# TPS65217DRSLR.net
KiCad netlist of a schematic drawn in Altium Designer
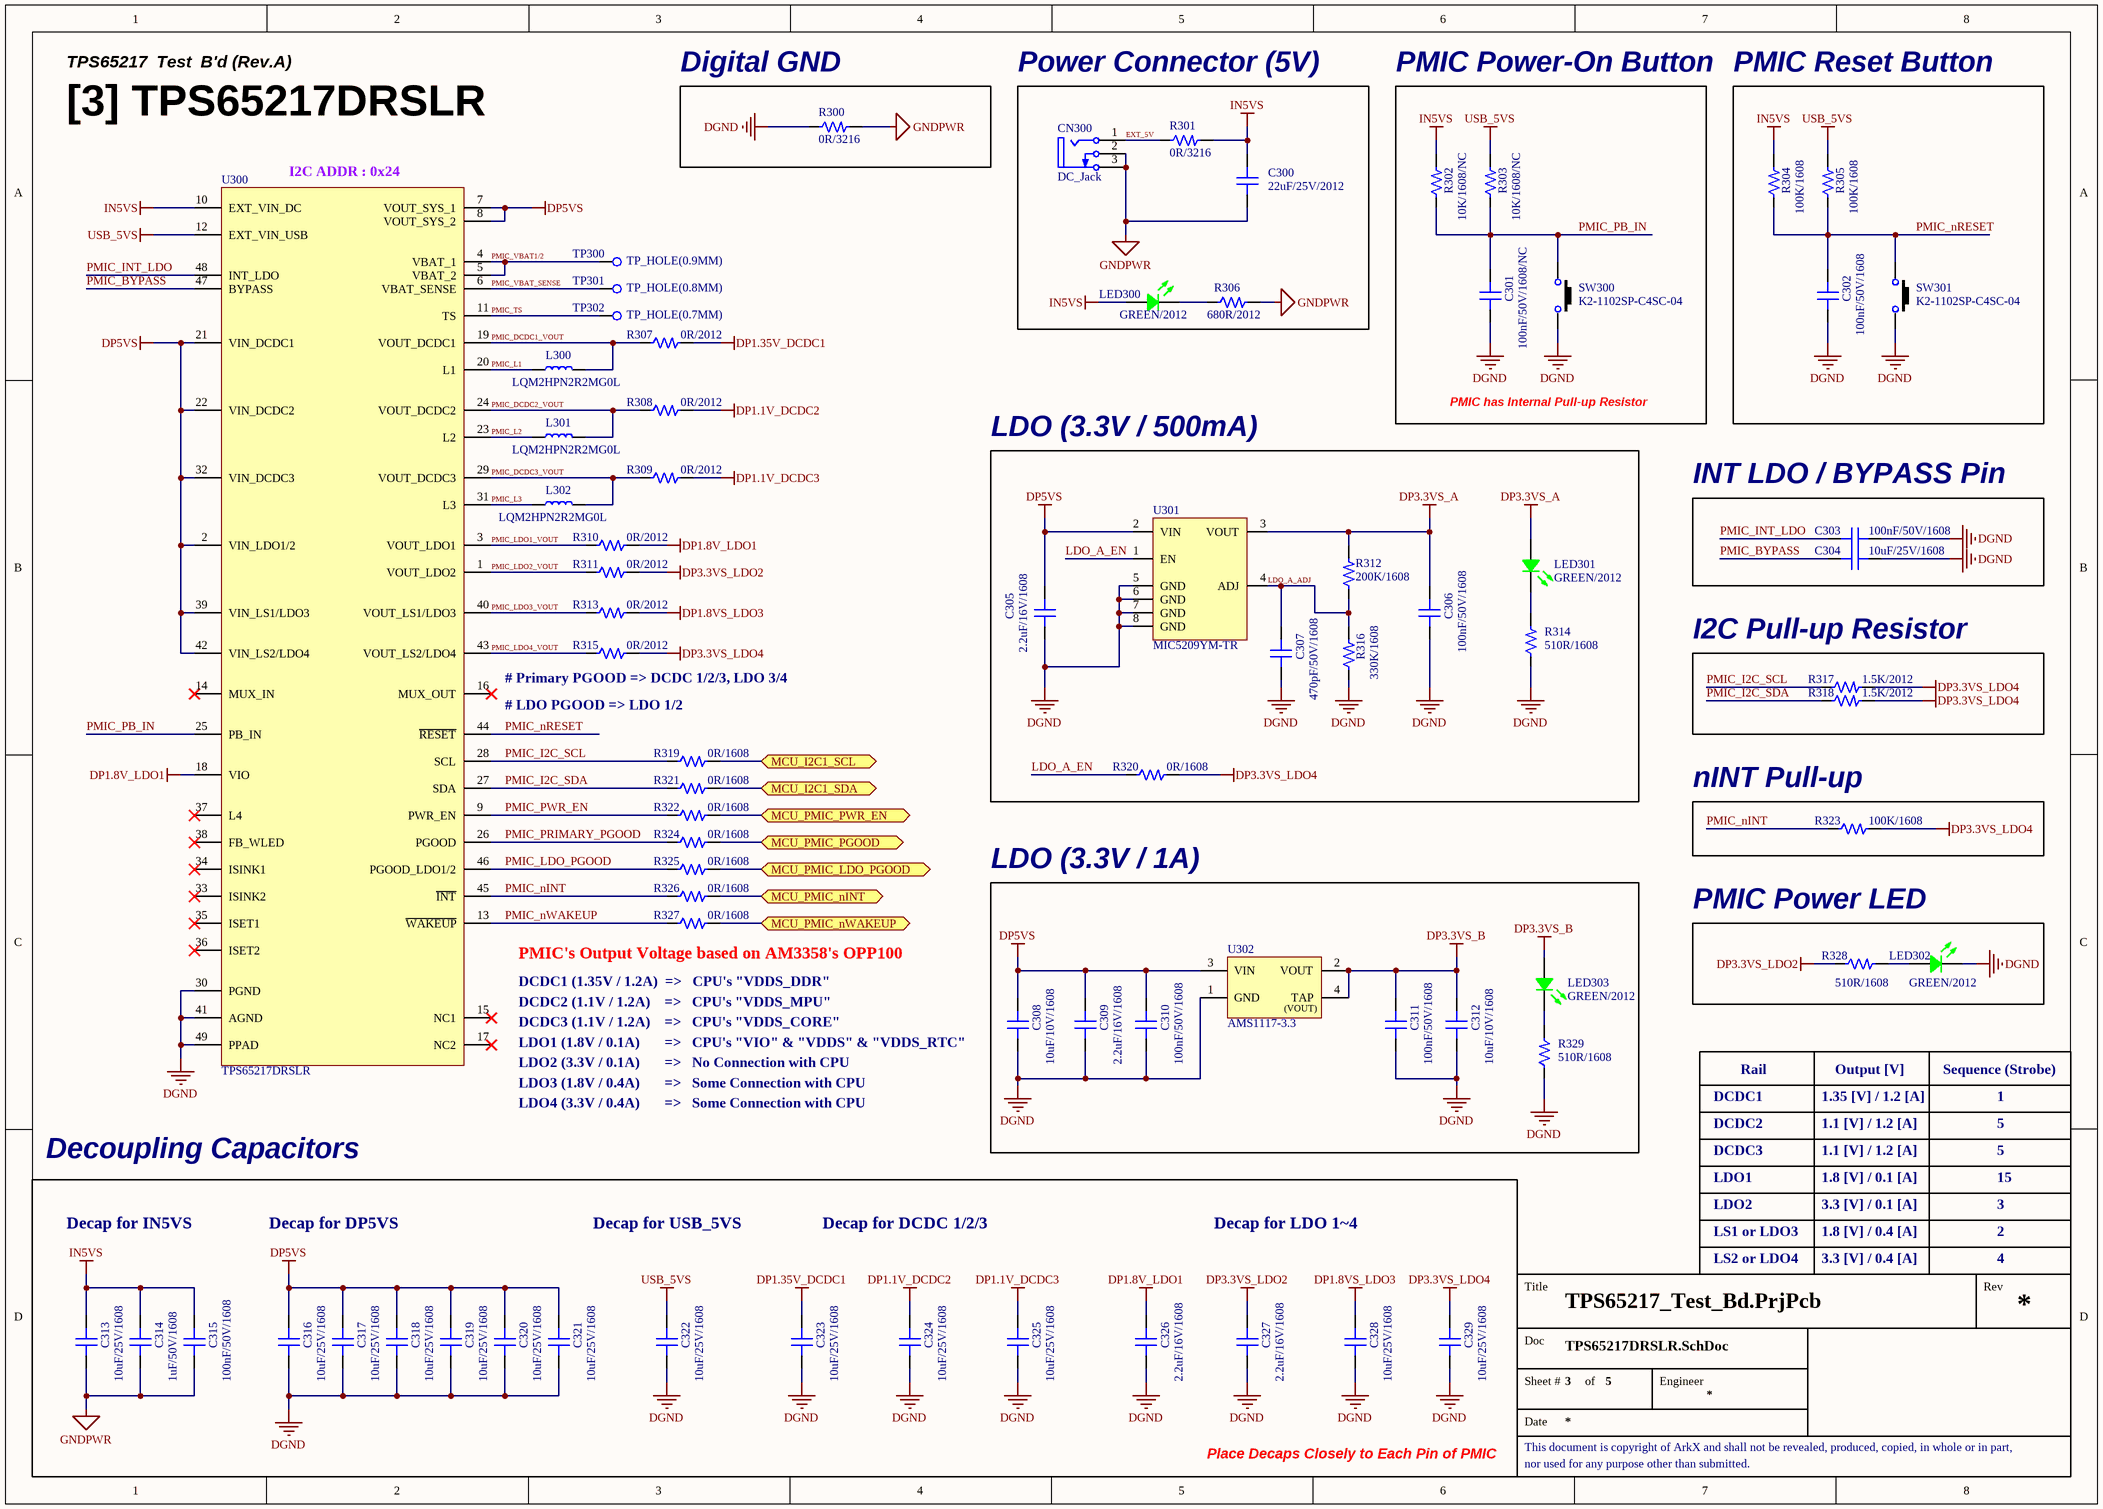
[diagram p0: TPS65217DRSLR.SchDoc]

(export (version "E")
  (design (tool "Eeschema 10.0.6"))
  (components
    (comp (ref "C300")
      (value "22uF/25V/2012")
      (footprint "CAP 2012 (0805_INCH)")
      (description "Ceramic CAP_22uF/25V/2012")
      (fields (field (name "LCSC PART #") "C45783"))
      (libsource (lib "Arkx") (part "CAP_22uF/25V/2012"))
    )
    (comp (ref "C301")
      (value "100nF/50V/1608/NC")
      (footprint "CAP 1608 (0603_INCH)/NC")
      (description "Ceramic CAP_100nF/50V/1608")
      (libsource (lib "Arkx") (part "CAP_NC_100nF/50V/1608"))
    )
    (comp (ref "C302")
      (value "100nF/50V/1608")
      (footprint "CAP 1608 (0603_INCH)")
      (description "Ceramic CAP_100nF/50V/1608")
      (fields (field (name "LCSC PART #") "C14663"))
      (libsource (lib "Arkx") (part "CAP_100nF/50V/1608"))
    )
    (comp (ref "C303")
      (value "100nF/50V/1608")
      (footprint "CAP 1608 (0603_INCH)")
      (description "Ceramic CAP_100nF/50V/1608")
      (fields (field (name "LCSC PART #") "C14663"))
      (libsource (lib "Arkx") (part "CAP_100nF/50V/1608"))
    )
    (comp (ref "C304")
      (value "10uF/25V/1608")
      (footprint "CAP 1608 (0603_INCH)")
      (description "Ceramic CAP_10uF/25V/1608")
      (fields (field (name "LCSC PART #") "C96446"))
      (libsource (lib "Arkx") (part "CAP_10uF/25V/1608"))
    )
    (comp (ref "C305")
      (value "2.2uF/16V/1608")
      (footprint "CAP 1608 (0603_INCH)")
      (description "Ceramic CAP_2.2uF/16V/1608")
      (fields (field (name "LCSC PART #") "C23630"))
      (libsource (lib "Arkx") (part "CAP_2.2uF/16V/1608"))
    )
    (comp (ref "C306")
      (value "100nF/50V/1608")
      (footprint "CAP 1608 (0603_INCH)")
      (description "Ceramic CAP_100nF/50V/1608")
      (fields (field (name "LCSC PART #") "C14663"))
      (libsource (lib "Arkx") (part "CAP_100nF/50V/1608"))
    )
    (comp (ref "C307")
      (value "470pF/50V/1608")
      (footprint "CAP 1608 (0603_INCH)")
      (description "Ceramic CAP_470pF/50V/1608")
      (fields (field (name "LCSC PART #") "C1620"))
      (libsource (lib "Arkx") (part "CAP_470pF/50V/1608"))
    )
    (comp (ref "C308")
      (value "10uF/10V/1608")
      (footprint "CAP 1608 (0603_INCH)")
      (description "Ceramic CAP_10uF/10V/1608")
      (fields (field (name "LCSC PART #") "C19702"))
      (libsource (lib "Arkx") (part "CAP_10uF/10V/1608"))
    )
    (comp (ref "C309")
      (value "2.2uF/16V/1608")
      (footprint "CAP 1608 (0603_INCH)")
      (description "Ceramic CAP_2.2uF/16V/1608")
      (fields (field (name "LCSC PART #") "C23630"))
      (libsource (lib "Arkx") (part "CAP_2.2uF/16V/1608"))
    )
    (comp (ref "C310")
      (value "100nF/50V/1608")
      (footprint "CAP 1608 (0603_INCH)")
      (description "Ceramic CAP_100nF/50V/1608")
      (fields (field (name "LCSC PART #") "C14663"))
      (libsource (lib "Arkx") (part "CAP_100nF/50V/1608"))
    )
    (comp (ref "C311")
      (value "100nF/50V/1608")
      (footprint "CAP 1608 (0603_INCH)")
      (description "Ceramic CAP_100nF/50V/1608")
      (fields (field (name "LCSC PART #") "C14663"))
      (libsource (lib "Arkx") (part "CAP_100nF/50V/1608"))
    )
    (comp (ref "C312")
      (value "10uF/10V/1608")
      (footprint "CAP 1608 (0603_INCH)")
      (description "Ceramic CAP_10uF/10V/1608")
      (fields (field (name "LCSC PART #") "C19702"))
      (libsource (lib "Arkx") (part "CAP_10uF/10V/1608"))
    )
    (comp (ref "C313")
      (value "10uF/25V/1608")
      (footprint "CAP 1608 (0603_INCH)")
      (description "Ceramic CAP_10uF/25V/1608")
      (fields (field (name "LCSC PART #") "C96446"))
      (libsource (lib "Arkx") (part "CAP_10uF/25V/1608"))
    )
    (comp (ref "C314")
      (value "1uF/50V/1608")
      (footprint "CAP 1608 (0603_INCH)")
      (description "Ceramic CAP_1uF/50V/1608")
      (fields (field (name "LCSC PART #") "C15849"))
      (libsource (lib "Arkx") (part "CAP_1uF/50V/1608"))
    )
    (comp (ref "C315")
      (value "100nF/50V/1608")
      (footprint "CAP 1608 (0603_INCH)")
      (description "Ceramic CAP_100nF/50V/1608")
      (fields (field (name "LCSC PART #") "C14663"))
      (libsource (lib "Arkx") (part "CAP_100nF/50V/1608"))
    )
    (comp (ref "C316")
      (value "10uF/25V/1608")
      (footprint "CAP 1608 (0603_INCH)")
      (description "Ceramic CAP_10uF/25V/1608")
      (fields (field (name "LCSC PART #") "C96446"))
      (libsource (lib "Arkx") (part "CAP_10uF/25V/1608"))
    )
    (comp (ref "C317")
      (value "10uF/25V/1608")
      (footprint "CAP 1608 (0603_INCH)")
      (description "Ceramic CAP_10uF/25V/1608")
      (fields (field (name "LCSC PART #") "C96446"))
      (libsource (lib "Arkx") (part "CAP_10uF/25V/1608"))
    )
    (comp (ref "C318")
      (value "10uF/25V/1608")
      (footprint "CAP 1608 (0603_INCH)")
      (description "Ceramic CAP_10uF/25V/1608")
      (fields (field (name "LCSC PART #") "C96446"))
      (libsource (lib "Arkx") (part "CAP_10uF/25V/1608"))
    )
    (comp (ref "C319")
      (value "10uF/25V/1608")
      (footprint "CAP 1608 (0603_INCH)")
      (description "Ceramic CAP_10uF/25V/1608")
      (fields (field (name "LCSC PART #") "C96446"))
      (libsource (lib "Arkx") (part "CAP_10uF/25V/1608"))
    )
    (comp (ref "C320")
      (value "10uF/25V/1608")
      (footprint "CAP 1608 (0603_INCH)")
      (description "Ceramic CAP_10uF/25V/1608")
      (fields (field (name "LCSC PART #") "C96446"))
      (libsource (lib "Arkx") (part "CAP_10uF/25V/1608"))
    )
    (comp (ref "C321")
      (value "10uF/25V/1608")
      (footprint "CAP 1608 (0603_INCH)")
      (description "Ceramic CAP_10uF/25V/1608")
      (fields (field (name "LCSC PART #") "C96446"))
      (libsource (lib "Arkx") (part "CAP_10uF/25V/1608"))
    )
    (comp (ref "C322")
      (value "10uF/25V/1608")
      (footprint "CAP 1608 (0603_INCH)")
      (description "Ceramic CAP_10uF/25V/1608")
      (fields (field (name "LCSC PART #") "C96446"))
      (libsource (lib "Arkx") (part "CAP_10uF/25V/1608"))
    )
    (comp (ref "C323")
      (value "10uF/25V/1608")
      (footprint "CAP 1608 (0603_INCH)")
      (description "Ceramic CAP_10uF/25V/1608")
      (fields (field (name "LCSC PART #") "C96446"))
      (libsource (lib "Arkx") (part "CAP_10uF/25V/1608"))
    )
    (comp (ref "C324")
      (value "10uF/25V/1608")
      (footprint "CAP 1608 (0603_INCH)")
      (description "Ceramic CAP_10uF/25V/1608")
      (fields (field (name "LCSC PART #") "C96446"))
      (libsource (lib "Arkx") (part "CAP_10uF/25V/1608"))
    )
    (comp (ref "C325")
      (value "10uF/25V/1608")
      (footprint "CAP 1608 (0603_INCH)")
      (description "Ceramic CAP_10uF/25V/1608")
      (fields (field (name "LCSC PART #") "C96446"))
      (libsource (lib "Arkx") (part "CAP_10uF/25V/1608"))
    )
    (comp (ref "C326")
      (value "2.2uF/16V/1608")
      (footprint "CAP 1608 (0603_INCH)")
      (description "Ceramic CAP_2.2uF/16V/1608")
      (fields (field (name "LCSC PART #") "C23630"))
      (libsource (lib "Arkx") (part "CAP_2.2uF/16V/1608"))
    )
    (comp (ref "C327")
      (value "2.2uF/16V/1608")
      (footprint "CAP 1608 (0603_INCH)")
      (description "Ceramic CAP_2.2uF/16V/1608")
      (fields (field (name "LCSC PART #") "C23630"))
      (libsource (lib "Arkx") (part "CAP_2.2uF/16V/1608"))
    )
    (comp (ref "C328")
      (value "10uF/25V/1608")
      (footprint "CAP 1608 (0603_INCH)")
      (description "Ceramic CAP_10uF/25V/1608")
      (fields (field (name "LCSC PART #") "C96446"))
      (libsource (lib "Arkx") (part "CAP_10uF/25V/1608"))
    )
    (comp (ref "C329")
      (value "10uF/25V/1608")
      (footprint "CAP 1608 (0603_INCH)")
      (description "Ceramic CAP_10uF/25V/1608")
      (fields (field (name "LCSC PART #") "C96446"))
      (libsource (lib "Arkx") (part "CAP_10uF/25V/1608"))
    )
    (comp (ref "CN300")
      (value "DC_Jack")
      (footprint "CON_DC-JACK")
      (libsource (lib "Arkx") (part "CON_DC-Jack"))
    )
    (comp (ref "L300")
      (value "LQM2HPN2R2MG0L")
      (footprint "IND_LQM2HPN2R2MG0L")
      (description "2.2 µH Shielded Multilayer Inductor 1.3 A 100mOhm Max 1008 (2520 Metric)")
      (fields (field (name "LCSC PART #") "C86092"))
      (libsource (lib "Arkx") (part "IND_LQM2HPN2R2MG0L"))
    )
    (comp (ref "L301")
      (value "LQM2HPN2R2MG0L")
      (footprint "IND_LQM2HPN2R2MG0L")
      (description "2.2 µH Shielded Multilayer Inductor 1.3 A 100mOhm Max 1008 (2520 Metric)")
      (fields (field (name "LCSC PART #") "C86092"))
      (libsource (lib "Arkx") (part "IND_LQM2HPN2R2MG0L"))
    )
    (comp (ref "L302")
      (value "LQM2HPN2R2MG0L")
      (footprint "IND_LQM2HPN2R2MG0L")
      (description "2.2 µH Shielded Multilayer Inductor 1.3 A 100mOhm Max 1008 (2520 Metric)")
      (fields (field (name "LCSC PART #") "C86092"))
      (libsource (lib "Arkx") (part "IND_LQM2HPN2R2MG0L"))
    )
    (comp (ref "LED300")
      (value "GREEN/2012")
      (footprint "LED MHT170RGBCT (GREEN)")
      (fields (field (name "LCSC PART #") "C2962094"))
      (libsource (lib "Arkx") (part "LED_MHT170RGBCT(GREEN)"))
    )
    (comp (ref "LED301")
      (value "GREEN/2012")
      (footprint "LED MHT170RGBCT (GREEN)")
      (fields (field (name "LCSC PART #") "C2962094"))
      (libsource (lib "Arkx") (part "LED_MHT170RGBCT(GREEN)"))
    )
    (comp (ref "LED302")
      (value "GREEN/2012")
      (footprint "LED MHT170RGBCT (GREEN)")
      (fields (field (name "LCSC PART #") "C2962094"))
      (libsource (lib "Arkx") (part "LED_MHT170RGBCT(GREEN)"))
    )
    (comp (ref "LED303")
      (value "GREEN/2012")
      (footprint "LED MHT170RGBCT (GREEN)")
      (fields (field (name "LCSC PART #") "C2962094"))
      (libsource (lib "Arkx") (part "LED_MHT170RGBCT(GREEN)"))
    )
    (comp (ref "R300")
      (value "0R/3216")
      (footprint "RES 3216 (1206_inch)")
      (description "RES_0R/3216/0.25W")
      (fields (field (name "LCSC PART #") "C17888"))
      (libsource (lib "Arkx") (part "RES_0R/3216/0.25W"))
    )
    (comp (ref "R301")
      (value "0R/3216")
      (footprint "RES 3216 (1206_inch)")
      (description "RES_0R/3216/0.25W")
      (fields (field (name "LCSC PART #") "C17888"))
      (libsource (lib "Arkx") (part "RES_0R/3216/0.25W"))
    )
    (comp (ref "R302")
      (value "10K/1608/NC")
      (footprint "RES 1608 (0603_inch)/NC")
      (description "RES_10K/1608/0.1W")
      (libsource (lib "Arkx") (part "RES_NC_10K/1608/0.1W"))
    )
    (comp (ref "R303")
      (value "10K/1608/NC")
      (footprint "RES 1608 (0603_inch)/NC")
      (description "RES_10K/1608/0.1W")
      (libsource (lib "Arkx") (part "RES_NC_10K/1608/0.1W"))
    )
    (comp (ref "R304")
      (value "100K/1608")
      (footprint "RES 1608 (0603_inch)")
      (description "RES_100K/1608/0.1W")
      (fields (field (name "LCSC PART #") "C25803"))
      (libsource (lib "Arkx") (part "RES_100K/1608/0.1W"))
    )
    (comp (ref "R305")
      (value "100K/1608")
      (footprint "RES 1608 (0603_inch)")
      (description "RES_100K/1608/0.1W")
      (fields (field (name "LCSC PART #") "C25803"))
      (libsource (lib "Arkx") (part "RES_100K/1608/0.1W"))
    )
    (comp (ref "R306")
      (value "680R/2012")
      (footprint "RES 2012 (0805_inch)")
      (description "RES_680R/2012/0.125W")
      (fields (field (name "LCSC PART #") "C17798"))
      (libsource (lib "Arkx") (part "RES_680R/2012/0.125W"))
    )
    (comp (ref "R307")
      (value "0R/2012")
      (footprint "RES 2012 (0805_inch)")
      (description "RES_0R/2012/0.125W")
      (fields (field (name "LCSC PART #") "C17477"))
      (libsource (lib "Arkx") (part "RES_0R/2012/0.125W"))
    )
    (comp (ref "R308")
      (value "0R/2012")
      (footprint "RES 2012 (0805_inch)")
      (description "RES_0R/2012/0.125W")
      (fields (field (name "LCSC PART #") "C17477"))
      (libsource (lib "Arkx") (part "RES_0R/2012/0.125W"))
    )
    (comp (ref "R309")
      (value "0R/2012")
      (footprint "RES 2012 (0805_inch)")
      (description "RES_0R/2012/0.125W")
      (fields (field (name "LCSC PART #") "C17477"))
      (libsource (lib "Arkx") (part "RES_0R/2012/0.125W"))
    )
    (comp (ref "R310")
      (value "0R/2012")
      (footprint "RES 2012 (0805_inch)")
      (description "RES_0R/2012/0.125W")
      (fields (field (name "LCSC PART #") "C17477"))
      (libsource (lib "Arkx") (part "RES_0R/2012/0.125W"))
    )
    (comp (ref "R311")
      (value "0R/2012")
      (footprint "RES 2012 (0805_inch)")
      (description "RES_0R/2012/0.125W")
      (fields (field (name "LCSC PART #") "C17477"))
      (libsource (lib "Arkx") (part "RES_0R/2012/0.125W"))
    )
    (comp (ref "R312")
      (value "200K/1608")
      (footprint "RES 1608 (0603_inch)")
      (description "RES_200K/1608/0.1W")
      (fields (field (name "LCSC PART #") "C25811"))
      (libsource (lib "Arkx") (part "RES_200K/1608/0.1W"))
    )
    (comp (ref "R313")
      (value "0R/2012")
      (footprint "RES 2012 (0805_inch)")
      (description "RES_0R/2012/0.125W")
      (fields (field (name "LCSC PART #") "C17477"))
      (libsource (lib "Arkx") (part "RES_0R/2012/0.125W"))
    )
    (comp (ref "R314")
      (value "510R/1608")
      (footprint "RES 1608 (0603_inch)")
      (description "RES_510R/1608/0.1W")
      (fields (field (name "LCSC PART #") "C23193"))
      (libsource (lib "Arkx") (part "RES_510R/1608/0.1W"))
    )
    (comp (ref "R315")
      (value "0R/2012")
      (footprint "RES 2012 (0805_inch)")
      (description "RES_0R/2012/0.125W")
      (fields (field (name "LCSC PART #") "C17477"))
      (libsource (lib "Arkx") (part "RES_0R/2012/0.125W"))
    )
    (comp (ref "R316")
      (value "330K/1608")
      (footprint "RES 1608 (0603_inch)")
      (description "RES_330K/1608/0.1W")
      (fields (field (name "LCSC PART #") "C23137"))
      (libsource (lib "Arkx") (part "RES_330K/1608/0.1W"))
    )
    (comp (ref "R317")
      (value "1.5K/2012")
      (footprint "RES 2012 (0805_inch)")
      (description "RES_1.5K/2012/0.125W")
      (fields (field (name "LCSC PART #") "C4310"))
      (libsource (lib "Arkx") (part "RES_1.5K/2012/0.125W"))
    )
    (comp (ref "R318")
      (value "1.5K/2012")
      (footprint "RES 2012 (0805_inch)")
      (description "RES_1.5K/2012/0.125W")
      (fields (field (name "LCSC PART #") "C4310"))
      (libsource (lib "Arkx") (part "RES_1.5K/2012/0.125W"))
    )
    (comp (ref "R319")
      (value "0R/1608")
      (footprint "RES 1608 (0603_inch)")
      (description "RES_0R/1608/0.1W")
      (fields (field (name "LCSC PART #") "C21189"))
      (libsource (lib "Arkx") (part "RES_0R/1608/0.1W"))
    )
    (comp (ref "R320")
      (value "0R/1608")
      (footprint "RES 1608 (0603_inch)")
      (description "RES_0R/1608/0.1W")
      (fields (field (name "LCSC PART #") "C21189"))
      (libsource (lib "Arkx") (part "RES_0R/1608/0.1W"))
    )
    (comp (ref "R321")
      (value "0R/1608")
      (footprint "RES 1608 (0603_inch)")
      (description "RES_0R/1608/0.1W")
      (fields (field (name "LCSC PART #") "C21189"))
      (libsource (lib "Arkx") (part "RES_0R/1608/0.1W"))
    )
    (comp (ref "R322")
      (value "0R/1608")
      (footprint "RES 1608 (0603_inch)")
      (description "RES_0R/1608/0.1W")
      (fields (field (name "LCSC PART #") "C21189"))
      (libsource (lib "Arkx") (part "RES_0R/1608/0.1W"))
    )
    (comp (ref "R323")
      (value "100K/1608")
      (footprint "RES 1608 (0603_inch)")
      (description "RES_100K/1608/0.1W")
      (fields (field (name "LCSC PART #") "C25803"))
      (libsource (lib "Arkx") (part "RES_100K/1608/0.1W"))
    )
    (comp (ref "R324")
      (value "0R/1608")
      (footprint "RES 1608 (0603_inch)")
      (description "RES_0R/1608/0.1W")
      (fields (field (name "LCSC PART #") "C21189"))
      (libsource (lib "Arkx") (part "RES_0R/1608/0.1W"))
    )
    (comp (ref "R325")
      (value "0R/1608")
      (footprint "RES 1608 (0603_inch)")
      (description "RES_0R/1608/0.1W")
      (fields (field (name "LCSC PART #") "C21189"))
      (libsource (lib "Arkx") (part "RES_0R/1608/0.1W"))
    )
    (comp (ref "R326")
      (value "0R/1608")
      (footprint "RES 1608 (0603_inch)")
      (description "RES_0R/1608/0.1W")
      (fields (field (name "LCSC PART #") "C21189"))
      (libsource (lib "Arkx") (part "RES_0R/1608/0.1W"))
    )
    (comp (ref "R327")
      (value "0R/1608")
      (footprint "RES 1608 (0603_inch)")
      (description "RES_0R/1608/0.1W")
      (fields (field (name "LCSC PART #") "C21189"))
      (libsource (lib "Arkx") (part "RES_0R/1608/0.1W"))
    )
    (comp (ref "R328")
      (value "510R/1608")
      (footprint "RES 1608 (0603_inch)")
      (description "RES_510R/1608/0.1W")
      (fields (field (name "LCSC PART #") "C23193"))
      (libsource (lib "Arkx") (part "RES_510R/1608/0.1W"))
    )
    (comp (ref "R329")
      (value "510R/1608")
      (footprint "RES 1608 (0603_inch)")
      (description "RES_510R/1608/0.1W")
      (fields (field (name "LCSC PART #") "C23193"))
      (libsource (lib "Arkx") (part "RES_510R/1608/0.1W"))
    )
    (comp (ref "SW300")
      (value "K2-1102SP-C4SC-04")
      (footprint "SW K2-1102SP-C4SC-04")
      (fields (field (name "LCSC PART #") "C127509"))
      (libsource (lib "Arkx") (part "SW_K2-1102SP-C4SC-04(2P)"))
    )
    (comp (ref "SW301")
      (value "K2-1102SP-C4SC-04")
      (footprint "SW K2-1102SP-C4SC-04")
      (fields (field (name "LCSC PART #") "C127509"))
      (libsource (lib "Arkx") (part "SW_K2-1102SP-C4SC-04(2P)"))
    )
    (comp (ref "TP300")
      (value "TP_HOLE(0.9MM)")
      (footprint "TP_HOLE(0.9MM)")
      (libsource (lib "Arkx") (part "TP_HOLE(0.9MM)"))
    )
    (comp (ref "TP301")
      (value "TP_HOLE(0.8MM)")
      (footprint "TP_HOLE(0.8MM)")
      (libsource (lib "Arkx") (part "TP_HOLE(0.8MM)"))
    )
    (comp (ref "TP302")
      (value "TP_HOLE(0.7MM)")
      (footprint "TP_HOLE(0.7MM)")
      (libsource (lib "Arkx") (part "TP_HOLE(0.7MM)"))
    )
    (comp (ref "U300")
      (value "TPS65217DRSLR")
      (footprint "IC_VQFN-48(6x6)")
      (fields (field (name "LCSC PART #") "C702315"))
      (libsource (lib "Arkx") (part "IC_PMIC_TPS65217DRSLR"))
    )
    (comp (ref "U301")
      (value "MIC5209YM-TR")
      (footprint "IC_SOIC-8 (4.90x3.90mm)")
      (description "Linear Voltage Regulator IC Positive Adjustable 1 Output 500mA 8-SOIC")
      (fields (field (name "LCSC PART #") "C461593"))
      (libsource (lib "Arkx") (part "IC_REG_MIC5209YM-TR"))
    )
    (comp (ref "U302")
      (value "AMS1117-3.3")
      (footprint "SOT 223-3 (DIODES INCORPORATED)")
      (fields (field (name "LCSC PART #") "C6186"))
      (libsource (lib "Arkx") (part "IC_REG_AMS1117-3.3"))
    )
  )
  (nets
    (net (code "1") (name "/EXT_5V") (class "Default")
      (node (ref "CN300") (pin "1") (pinfunction "VCC_1") (pintype "power_in"))
      (node (ref "R301") (pin "1") (pinfunction "1_1") (pintype "passive"))
    )
    (net (code "2") (name "/LDO_A_ADJ") (class "Default")
      (node (ref "C307") (pin "2") (pinfunction "2_2") (pintype "passive"))
      (node (ref "R312") (pin "1") (pinfunction "1_1") (pintype "passive"))
      (node (ref "R316") (pin "2") (pinfunction "2_2") (pintype "passive"))
      (node (ref "U301") (pin "4") (pinfunction "ADJ_4") (pintype "passive"))
    )
    (net (code "3") (name "/LDO_A_EN") (class "Default")
      (node (ref "R320") (pin "1") (pinfunction "1_1") (pintype "passive"))
      (node (ref "U301") (pin "1") (pinfunction "EN_1") (pintype "passive"))
    )
    (net (code "4") (name "/MCU_I2C1_SCL") (class "Default")
      (node (ref "R319") (pin "2") (pinfunction "2_2") (pintype "passive"))
    )
    (net (code "5") (name "/MCU_I2C1_SDA") (class "Default")
      (node (ref "R321") (pin "2") (pinfunction "2_2") (pintype "passive"))
    )
    (net (code "6") (name "/MCU_PMIC_LDO_PGOOD") (class "Default")
      (node (ref "R325") (pin "2") (pinfunction "2_2") (pintype "passive"))
    )
    (net (code "7") (name "/MCU_PMIC_PGOOD") (class "Default")
      (node (ref "R324") (pin "2") (pinfunction "2_2") (pintype "passive"))
    )
    (net (code "8") (name "/MCU_PMIC_PWR_EN") (class "Default")
      (node (ref "R322") (pin "2") (pinfunction "2_2") (pintype "passive"))
    )
    (net (code "9") (name "/MCU_PMIC_nINT") (class "Default")
      (node (ref "R326") (pin "2") (pinfunction "2_2") (pintype "passive"))
    )
    (net (code "10") (name "/MCU_PMIC_nWAKEUP") (class "Default")
      (node (ref "R327") (pin "2") (pinfunction "2_2") (pintype "passive"))
    )
    (net (code "11") (name "/PMIC_BYPASS") (class "Default")
      (node (ref "C304") (pin "2") (pinfunction "2_2") (pintype "passive"))
      (node (ref "U300") (pin "47") (pinfunction "BYPASS_47") (pintype "passive"))
    )
    (net (code "12") (name "/PMIC_DCDC1_VOUT") (class "Default")
      (node (ref "L300") (pin "2") (pinfunction "2_2") (pintype "passive"))
      (node (ref "R307") (pin "1") (pinfunction "1_1") (pintype "passive"))
      (node (ref "U300") (pin "19") (pinfunction "VOUT_DCDC1_19") (pintype "passive"))
    )
    (net (code "13") (name "/PMIC_DCDC2_VOUT") (class "Default")
      (node (ref "L301") (pin "2") (pinfunction "2_2") (pintype "passive"))
      (node (ref "R308") (pin "1") (pinfunction "1_1") (pintype "passive"))
      (node (ref "U300") (pin "24") (pinfunction "VOUT_DCDC2_24") (pintype "passive"))
    )
    (net (code "14") (name "/PMIC_DCDC3_VOUT") (class "Default")
      (node (ref "L302") (pin "2") (pinfunction "2_2") (pintype "passive"))
      (node (ref "R309") (pin "1") (pinfunction "1_1") (pintype "passive"))
      (node (ref "U300") (pin "29") (pinfunction "VOUT_DCDC3_29") (pintype "passive"))
    )
    (net (code "15") (name "/PMIC_I2C_SCL") (class "Default")
      (node (ref "R317") (pin "1") (pinfunction "1_1") (pintype "passive"))
      (node (ref "R319") (pin "1") (pinfunction "1_1") (pintype "passive"))
      (node (ref "U300") (pin "28") (pinfunction "SCL_28") (pintype "passive"))
    )
    (net (code "16") (name "/PMIC_I2C_SDA") (class "Default")
      (node (ref "R318") (pin "1") (pinfunction "1_1") (pintype "passive"))
      (node (ref "R321") (pin "1") (pinfunction "1_1") (pintype "passive"))
      (node (ref "U300") (pin "27") (pinfunction "SDA_27") (pintype "passive"))
    )
    (net (code "17") (name "/PMIC_INT_LDO") (class "Default")
      (node (ref "C303") (pin "2") (pinfunction "2_2") (pintype "passive"))
      (node (ref "U300") (pin "48") (pinfunction "INT_LDO_48") (pintype "passive"))
    )
    (net (code "18") (name "/PMIC_L1") (class "Default")
      (node (ref "L300") (pin "1") (pinfunction "1_1") (pintype "passive"))
      (node (ref "U300") (pin "20") (pinfunction "L1_20") (pintype "passive"))
    )
    (net (code "19") (name "/PMIC_L2") (class "Default")
      (node (ref "L301") (pin "1") (pinfunction "1_1") (pintype "passive"))
      (node (ref "U300") (pin "23") (pinfunction "L2_23") (pintype "passive"))
    )
    (net (code "20") (name "/PMIC_L3") (class "Default")
      (node (ref "L302") (pin "1") (pinfunction "1_1") (pintype "passive"))
      (node (ref "U300") (pin "31") (pinfunction "L3_31") (pintype "passive"))
    )
    (net (code "21") (name "/PMIC_LDO1_VOUT") (class "Default")
      (node (ref "R310") (pin "1") (pinfunction "1_1") (pintype "passive"))
      (node (ref "U300") (pin "3") (pinfunction "VOUT_LDO1_3") (pintype "passive"))
    )
    (net (code "22") (name "/PMIC_LDO2_VOUT") (class "Default")
      (node (ref "R311") (pin "1") (pinfunction "1_1") (pintype "passive"))
      (node (ref "U300") (pin "1") (pinfunction "VOUT_LDO2_1") (pintype "passive"))
    )
    (net (code "23") (name "/PMIC_LDO3_VOUT") (class "Default")
      (node (ref "R313") (pin "1") (pinfunction "1_1") (pintype "passive"))
      (node (ref "U300") (pin "40") (pinfunction "VOUT_LS1/LDO3_40") (pintype "passive"))
    )
    (net (code "24") (name "/PMIC_LDO4_VOUT") (class "Default")
      (node (ref "R315") (pin "1") (pinfunction "1_1") (pintype "passive"))
      (node (ref "U300") (pin "43") (pinfunction "VOUT_LS2/LDO4_43") (pintype "passive"))
    )
    (net (code "25") (name "/PMIC_LDO_PGOOD") (class "Default")
      (node (ref "R325") (pin "1") (pinfunction "1_1") (pintype "passive"))
      (node (ref "U300") (pin "46") (pinfunction "PGOOD_LDO1/2_46") (pintype "passive"))
    )
    (net (code "26") (name "/PMIC_PB_IN") (class "Default")
      (node (ref "C301") (pin "2") (pinfunction "2_2") (pintype "passive"))
      (node (ref "R302") (pin "1") (pinfunction "1_1") (pintype "passive"))
      (node (ref "R303") (pin "1") (pinfunction "1_1") (pintype "passive"))
      (node (ref "SW300") (pin "1") (pinfunction "1_1") (pintype "passive"))
      (node (ref "U300") (pin "25") (pinfunction "PB_IN_25") (pintype "passive"))
    )
    (net (code "27") (name "/PMIC_PRIMARY_PGOOD") (class "Default")
      (node (ref "R324") (pin "1") (pinfunction "1_1") (pintype "passive"))
      (node (ref "U300") (pin "26") (pinfunction "PGOOD_26") (pintype "passive"))
    )
    (net (code "28") (name "/PMIC_PWR_EN") (class "Default")
      (node (ref "R322") (pin "1") (pinfunction "1_1") (pintype "passive"))
      (node (ref "U300") (pin "9") (pinfunction "PWR_EN_9") (pintype "passive"))
    )
    (net (code "29") (name "/PMIC_TS") (class "Default")
      (node (ref "TP302") (pin "1") (pinfunction "TP_1") (pintype "passive"))
      (node (ref "U300") (pin "11") (pinfunction "TS_11") (pintype "passive"))
    )
    (net (code "30") (name "/PMIC_VBAT1{slash}2") (class "Default")
      (node (ref "TP300") (pin "1") (pinfunction "TP_1") (pintype "passive"))
      (node (ref "U300") (pin "4") (pinfunction "VBAT_1_4") (pintype "passive"))
      (node (ref "U300") (pin "5") (pinfunction "VBAT_2_5") (pintype "passive"))
    )
    (net (code "31") (name "/PMIC_VBAT_SENSE") (class "Default")
      (node (ref "TP301") (pin "1") (pinfunction "TP_1") (pintype "passive"))
      (node (ref "U300") (pin "6") (pinfunction "VBAT_SENSE_6") (pintype "passive"))
    )
    (net (code "32") (name "/PMIC_nINT") (class "Default")
      (node (ref "R323") (pin "1") (pinfunction "1_1") (pintype "passive"))
      (node (ref "R326") (pin "1") (pinfunction "1_1") (pintype "passive"))
      (node (ref "U300") (pin "45") (pinfunction "~{INT}_45") (pintype "passive"))
    )
    (net (code "33") (name "/PMIC_nRESET") (class "Default")
      (node (ref "C302") (pin "2") (pinfunction "2_2") (pintype "passive"))
      (node (ref "R304") (pin "1") (pinfunction "1_1") (pintype "passive"))
      (node (ref "R305") (pin "1") (pinfunction "1_1") (pintype "passive"))
      (node (ref "SW301") (pin "1") (pinfunction "1_1") (pintype "passive"))
      (node (ref "U300") (pin "44") (pinfunction "~{RESET}_44") (pintype "passive"))
    )
    (net (code "34") (name "/PMIC_nWAKEUP") (class "Default")
      (node (ref "R327") (pin "1") (pinfunction "1_1") (pintype "passive"))
      (node (ref "U300") (pin "13") (pinfunction "~{WAKEUP}_13") (pintype "passive"))
    )
    (net (code "35") (name "DGND") (class "Default")
      (node (ref "C301") (pin "1") (pinfunction "1_1") (pintype "passive"))
      (node (ref "C302") (pin "1") (pinfunction "1_1") (pintype "passive"))
      (node (ref "C303") (pin "1") (pinfunction "1_1") (pintype "passive"))
      (node (ref "C304") (pin "1") (pinfunction "1_1") (pintype "passive"))
      (node (ref "C305") (pin "1") (pinfunction "1_1") (pintype "passive"))
      (node (ref "C306") (pin "1") (pinfunction "1_1") (pintype "passive"))
      (node (ref "C307") (pin "1") (pinfunction "1_1") (pintype "passive"))
      (node (ref "C308") (pin "1") (pinfunction "1_1") (pintype "passive"))
      (node (ref "C309") (pin "1") (pinfunction "1_1") (pintype "passive"))
      (node (ref "C310") (pin "1") (pinfunction "1_1") (pintype "passive"))
      (node (ref "C311") (pin "1") (pinfunction "1_1") (pintype "passive"))
      (node (ref "C312") (pin "1") (pinfunction "1_1") (pintype "passive"))
      (node (ref "C316") (pin "1") (pinfunction "1_1") (pintype "passive"))
      (node (ref "C317") (pin "1") (pinfunction "1_1") (pintype "passive"))
      (node (ref "C318") (pin "1") (pinfunction "1_1") (pintype "passive"))
      (node (ref "C319") (pin "1") (pinfunction "1_1") (pintype "passive"))
      (node (ref "C320") (pin "1") (pinfunction "1_1") (pintype "passive"))
      (node (ref "C321") (pin "1") (pinfunction "1_1") (pintype "passive"))
      (node (ref "C322") (pin "1") (pinfunction "1_1") (pintype "passive"))
      (node (ref "C323") (pin "1") (pinfunction "1_1") (pintype "passive"))
      (node (ref "C324") (pin "1") (pinfunction "1_1") (pintype "passive"))
      (node (ref "C325") (pin "1") (pinfunction "1_1") (pintype "passive"))
      (node (ref "C326") (pin "1") (pinfunction "1_1") (pintype "passive"))
      (node (ref "C327") (pin "1") (pinfunction "1_1") (pintype "passive"))
      (node (ref "C328") (pin "1") (pinfunction "1_1") (pintype "passive"))
      (node (ref "C329") (pin "1") (pinfunction "1_1") (pintype "passive"))
      (node (ref "LED302") (pin "2") (pinfunction "GREEN_2") (pintype "passive"))
      (node (ref "R300") (pin "1") (pinfunction "1_1") (pintype "passive"))
      (node (ref "R314") (pin "1") (pinfunction "1_1") (pintype "passive"))
      (node (ref "R316") (pin "1") (pinfunction "1_1") (pintype "passive"))
      (node (ref "R329") (pin "1") (pinfunction "1_1") (pintype "passive"))
      (node (ref "SW300") (pin "3") (pinfunction "3_3") (pintype "passive"))
      (node (ref "SW301") (pin "3") (pinfunction "3_3") (pintype "passive"))
      (node (ref "U300") (pin "30") (pinfunction "PGND_30") (pintype "passive"))
      (node (ref "U300") (pin "41") (pinfunction "AGND_41") (pintype "passive"))
      (node (ref "U300") (pin "49") (pinfunction "PPAD_49") (pintype "passive"))
      (node (ref "U301") (pin "5") (pinfunction "GND_5") (pintype "power_in"))
      (node (ref "U301") (pin "6") (pinfunction "GND_6") (pintype "power_in"))
      (node (ref "U301") (pin "7") (pinfunction "GND_7") (pintype "power_in"))
      (node (ref "U301") (pin "8") (pinfunction "GND_8") (pintype "power_in"))
      (node (ref "U302") (pin "1") (pinfunction "GND_1") (pintype "passive"))
    )
    (net (code "36") (name "DP1.1V_DCDC2") (class "Default")
      (node (ref "C324") (pin "2") (pinfunction "2_2") (pintype "passive"))
      (node (ref "R308") (pin "2") (pinfunction "2_2") (pintype "passive"))
    )
    (net (code "37") (name "DP1.1V_DCDC3") (class "Default")
      (node (ref "C325") (pin "2") (pinfunction "2_2") (pintype "passive"))
      (node (ref "R309") (pin "2") (pinfunction "2_2") (pintype "passive"))
    )
    (net (code "38") (name "DP1.8VS_LDO3") (class "Default")
      (node (ref "C328") (pin "2") (pinfunction "2_2") (pintype "passive"))
      (node (ref "R313") (pin "2") (pinfunction "2_2") (pintype "passive"))
    )
    (net (code "39") (name "DP1.8V_LDO1") (class "Default")
      (node (ref "C326") (pin "2") (pinfunction "2_2") (pintype "passive"))
      (node (ref "R310") (pin "2") (pinfunction "2_2") (pintype "passive"))
      (node (ref "U300") (pin "18") (pinfunction "VIO_18") (pintype "passive"))
    )
    (net (code "40") (name "DP1.35V_DCDC1") (class "Default")
      (node (ref "C323") (pin "2") (pinfunction "2_2") (pintype "passive"))
      (node (ref "R307") (pin "2") (pinfunction "2_2") (pintype "passive"))
    )
    (net (code "41") (name "DP3.3VS_A") (class "Default")
      (node (ref "C306") (pin "2") (pinfunction "2_2") (pintype "passive"))
      (node (ref "LED301") (pin "4") (pinfunction "Common_Anode_4") (pintype "passive"))
      (node (ref "R312") (pin "2") (pinfunction "2_2") (pintype "passive"))
      (node (ref "U301") (pin "3") (pinfunction "VOUT_3") (pintype "power_in"))
    )
    (net (code "42") (name "DP3.3VS_B") (class "Default")
      (node (ref "C311") (pin "2") (pinfunction "2_2") (pintype "passive"))
      (node (ref "C312") (pin "2") (pinfunction "2_2") (pintype "passive"))
      (node (ref "LED303") (pin "4") (pinfunction "Common_Anode_4") (pintype "passive"))
      (node (ref "U302") (pin "2") (pinfunction "VOUT_2") (pintype "passive"))
      (node (ref "U302") (pin "4") (pinfunction "TAP_4") (pintype "passive"))
    )
    (net (code "43") (name "DP3.3VS_LDO2") (class "Default")
      (node (ref "C327") (pin "2") (pinfunction "2_2") (pintype "passive"))
      (node (ref "R311") (pin "2") (pinfunction "2_2") (pintype "passive"))
      (node (ref "R328") (pin "1") (pinfunction "1_1") (pintype "passive"))
    )
    (net (code "44") (name "DP3.3VS_LDO4") (class "Default")
      (node (ref "C329") (pin "2") (pinfunction "2_2") (pintype "passive"))
      (node (ref "R315") (pin "2") (pinfunction "2_2") (pintype "passive"))
      (node (ref "R317") (pin "2") (pinfunction "2_2") (pintype "passive"))
      (node (ref "R318") (pin "2") (pinfunction "2_2") (pintype "passive"))
      (node (ref "R320") (pin "2") (pinfunction "2_2") (pintype "passive"))
      (node (ref "R323") (pin "2") (pinfunction "2_2") (pintype "passive"))
    )
    (net (code "45") (name "DP5VS") (class "Default")
      (node (ref "C305") (pin "2") (pinfunction "2_2") (pintype "passive"))
      (node (ref "C308") (pin "2") (pinfunction "2_2") (pintype "passive"))
      (node (ref "C309") (pin "2") (pinfunction "2_2") (pintype "passive"))
      (node (ref "C310") (pin "2") (pinfunction "2_2") (pintype "passive"))
      (node (ref "C316") (pin "2") (pinfunction "2_2") (pintype "passive"))
      (node (ref "C317") (pin "2") (pinfunction "2_2") (pintype "passive"))
      (node (ref "C318") (pin "2") (pinfunction "2_2") (pintype "passive"))
      (node (ref "C319") (pin "2") (pinfunction "2_2") (pintype "passive"))
      (node (ref "C320") (pin "2") (pinfunction "2_2") (pintype "passive"))
      (node (ref "C321") (pin "2") (pinfunction "2_2") (pintype "passive"))
      (node (ref "U300") (pin "2") (pinfunction "VIN_LDO1/2_2") (pintype "passive"))
      (node (ref "U300") (pin "21") (pinfunction "VIN_DCDC1_21") (pintype "passive"))
      (node (ref "U300") (pin "22") (pinfunction "VIN_DCDC2_22") (pintype "passive"))
      (node (ref "U300") (pin "32") (pinfunction "VIN_DCDC3_32") (pintype "passive"))
      (node (ref "U300") (pin "39") (pinfunction "VIN_LS1/LDO3_39") (pintype "passive"))
      (node (ref "U300") (pin "42") (pinfunction "VIN_LS2/LDO4_42") (pintype "passive"))
      (node (ref "U300") (pin "7") (pinfunction "VOUT_SYS_1_7") (pintype "passive"))
      (node (ref "U300") (pin "8") (pinfunction "VOUT_SYS_2_8") (pintype "passive"))
      (node (ref "U301") (pin "2") (pinfunction "VIN_2") (pintype "power_in"))
      (node (ref "U302") (pin "3") (pinfunction "VIN_3") (pintype "passive"))
    )
    (net (code "46") (name "GNDPWR") (class "Default")
      (node (ref "C300") (pin "1") (pinfunction "1_1") (pintype "passive"))
      (node (ref "C313") (pin "1") (pinfunction "1_1") (pintype "passive"))
      (node (ref "C314") (pin "1") (pinfunction "1_1") (pintype "passive"))
      (node (ref "C315") (pin "1") (pinfunction "1_1") (pintype "passive"))
      (node (ref "CN300") (pin "2") (pinfunction "GND_2") (pintype "power_in"))
      (node (ref "CN300") (pin "3") (pinfunction "GND_3") (pintype "power_in"))
      (node (ref "R300") (pin "2") (pinfunction "2_2") (pintype "passive"))
      (node (ref "R306") (pin "2") (pinfunction "2_2") (pintype "passive"))
    )
    (net (code "47") (name "IN5VS") (class "Default")
      (node (ref "C300") (pin "2") (pinfunction "2_2") (pintype "passive"))
      (node (ref "C313") (pin "2") (pinfunction "2_2") (pintype "passive"))
      (node (ref "C314") (pin "2") (pinfunction "2_2") (pintype "passive"))
      (node (ref "C315") (pin "2") (pinfunction "2_2") (pintype "passive"))
      (node (ref "LED300") (pin "4") (pinfunction "Common_Anode_4") (pintype "passive"))
      (node (ref "R301") (pin "2") (pinfunction "2_2") (pintype "passive"))
      (node (ref "R302") (pin "2") (pinfunction "2_2") (pintype "passive"))
      (node (ref "R304") (pin "2") (pinfunction "2_2") (pintype "passive"))
      (node (ref "U300") (pin "10") (pinfunction "EXT_VIN_DC_10") (pintype "passive"))
    )
    (net (code "48") (name "Net-(LED300-GREEN)") (class "Default")
      (node (ref "LED300") (pin "2") (pinfunction "GREEN_2") (pintype "passive"))
      (node (ref "R306") (pin "1") (pinfunction "1_1") (pintype "passive"))
    )
    (net (code "49") (name "Net-(LED301-GREEN)") (class "Default")
      (node (ref "LED301") (pin "2") (pinfunction "GREEN_2") (pintype "passive"))
      (node (ref "R314") (pin "2") (pinfunction "2_2") (pintype "passive"))
    )
    (net (code "50") (name "Net-(LED302-Common_Anode)") (class "Default")
      (node (ref "LED302") (pin "4") (pinfunction "Common_Anode_4") (pintype "passive"))
      (node (ref "R328") (pin "2") (pinfunction "2_2") (pintype "passive"))
    )
    (net (code "51") (name "Net-(LED303-GREEN)") (class "Default")
      (node (ref "LED303") (pin "2") (pinfunction "GREEN_2") (pintype "passive"))
      (node (ref "R329") (pin "2") (pinfunction "2_2") (pintype "passive"))
    )
    (net (code "52") (name "USB_5VS") (class "Default")
      (node (ref "C322") (pin "2") (pinfunction "2_2") (pintype "passive"))
      (node (ref "R303") (pin "2") (pinfunction "2_2") (pintype "passive"))
      (node (ref "R305") (pin "2") (pinfunction "2_2") (pintype "passive"))
      (node (ref "U300") (pin "12") (pinfunction "EXT_VIN_USB_12") (pintype "passive"))
    )
    (net (code "53") (name "unconnected-(U300-FB_WLED-Pad38)") (class "Default")
      (node (ref "U300") (pin "38") (pinfunction "FB_WLED_38") (pintype "passive+no_connect"))
    )
    (net (code "54") (name "unconnected-(U300-ISET1-Pad35)") (class "Default")
      (node (ref "U300") (pin "35") (pinfunction "ISET1_35") (pintype "passive+no_connect"))
    )
    (net (code "55") (name "unconnected-(U300-ISET2-Pad36)") (class "Default")
      (node (ref "U300") (pin "36") (pinfunction "ISET2_36") (pintype "passive+no_connect"))
    )
    (net (code "56") (name "unconnected-(U300-ISINK1-Pad34)") (class "Default")
      (node (ref "U300") (pin "34") (pinfunction "ISINK1_34") (pintype "passive+no_connect"))
    )
    (net (code "57") (name "unconnected-(U300-ISINK2-Pad33)") (class "Default")
      (node (ref "U300") (pin "33") (pinfunction "ISINK2_33") (pintype "passive+no_connect"))
    )
    (net (code "58") (name "unconnected-(U300-L4-Pad37)") (class "Default")
      (node (ref "U300") (pin "37") (pinfunction "L4_37") (pintype "passive+no_connect"))
    )
    (net (code "59") (name "unconnected-(U300-MUX_IN-Pad14)") (class "Default")
      (node (ref "U300") (pin "14") (pinfunction "MUX_IN_14") (pintype "passive+no_connect"))
    )
    (net (code "60") (name "unconnected-(U300-MUX_OUT-Pad16)") (class "Default")
      (node (ref "U300") (pin "16") (pinfunction "MUX_OUT_16") (pintype "passive+no_connect"))
    )
    (net (code "61") (name "unconnected-(U300-NC1-Pad15)") (class "Default")
      (node (ref "U300") (pin "15") (pinfunction "NC1_15") (pintype "passive+no_connect"))
    )
    (net (code "62") (name "unconnected-(U300-NC2-Pad17)") (class "Default")
      (node (ref "U300") (pin "17") (pinfunction "NC2_17") (pintype "passive+no_connect"))
    )
  )
)
